# street_light.net
KiCad netlist of a schematic drawn in EAGLE
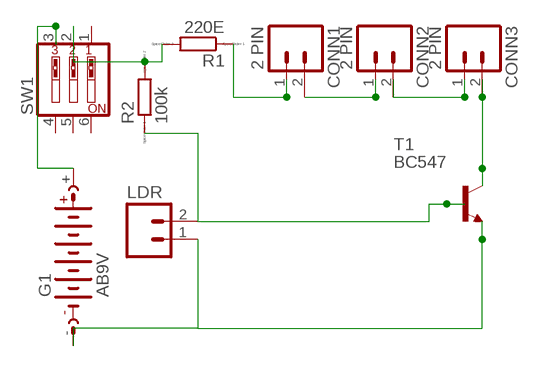
[diagram p0: schematic, sheet 1]

(export (version "E")
  (design (tool "Eeschema 10.0.6"))
  (components
    (comp (ref "CONN1")
      (value "2 PIN")
      (footprint "eagle-import:02P")
      (libsource (lib "eagle-import") (part "M02"))
    )
    (comp (ref "CONN2")
      (value "2 PIN")
      (footprint "eagle-import:02P")
      (libsource (lib "eagle-import") (part "M02"))
    )
    (comp (ref "CONN3")
      (value "2 PIN")
      (footprint "eagle-import:02P")
      (libsource (lib "eagle-import") (part "M02"))
    )
    (comp (ref "G1")
      (value "AB9V")
      (footprint "eagle-import:AB9V")
      (libsource (lib "eagle-import") (part "AB9V"))
    )
    (comp (ref "LDR")
      (value "M02")
      (footprint "eagle-import:02P")
      (libsource (lib "eagle-import") (part "M02"))
    )
    (comp (ref "R1")
      (value "220E")
      (footprint "eagle-import:0204_7")
      (libsource (lib "eagle-import") (part "R0204/7"))
    )
    (comp (ref "R2")
      (value "100k")
      (footprint "eagle-import:0204_7")
      (libsource (lib "eagle-import") (part "R0204/7"))
    )
    (comp (ref "SW1")
      (value "SW_DIP-3")
      (footprint "eagle-import:EDG-03")
      (libsource (lib "eagle-import") (part "SW_DIP-3"))
    )
    (comp (ref "T1")
      (value "BC547")
      (footprint "eagle-import:TO92")
      (libsource (lib "eagle-import") (part "BC547"))
    )
  )
  (nets
    (net (code "1") (name "Net-(CONN1-Pad1)") (class "Default")
      (node (ref "CONN1") (pin "1") (pinfunction "1_1") (pintype "passive"))
      (node (ref "R1") (pin "1") (pinfunction "1_1") (pintype "passive"))
    )
    (net (code "2") (name "Net-(CONN1-Pad2)") (class "Default")
      (node (ref "CONN1") (pin "2") (pinfunction "2_2") (pintype "passive"))
      (node (ref "CONN2") (pin "1") (pinfunction "1_1") (pintype "passive"))
    )
    (net (code "3") (name "Net-(CONN2-Pad2)") (class "Default")
      (node (ref "CONN2") (pin "2") (pinfunction "2_2") (pintype "passive"))
      (node (ref "CONN3") (pin "1") (pinfunction "1_1") (pintype "passive"))
    )
    (net (code "4") (name "Net-(G1-Pad+)") (class "Default")
      (node (ref "G1") (pin "+") (pinfunction "+_+") (pintype "passive"))
      (node (ref "SW1") (pin "3") (pinfunction "3_3") (pintype "passive"))
    )
    (net (code "5") (name "Net-(R1-Pad2)") (class "Default")
      (node (ref "R1") (pin "2") (pinfunction "2_2") (pintype "passive"))
      (node (ref "R2") (pin "2") (pinfunction "2_2") (pintype "passive"))
      (node (ref "SW1") (pin "2") (pinfunction "2_2") (pintype "passive"))
    )
    (net (code "6") (name "Net-(T1-B)") (class "Default")
      (node (ref "LDR") (pin "2") (pinfunction "2_2") (pintype "passive"))
      (node (ref "R2") (pin "1") (pinfunction "1_1") (pintype "passive"))
      (node (ref "T1") (pin "2") (pinfunction "B_2") (pintype "passive"))
    )
    (net (code "7") (name "Net-(T1-C)") (class "Default")
      (node (ref "CONN3") (pin "2") (pinfunction "2_2") (pintype "passive"))
      (node (ref "T1") (pin "3") (pinfunction "C_3") (pintype "passive"))
    )
    (net (code "8") (name "Net-(T1-E)") (class "Default")
      (node (ref "G1") (pin "-") (pinfunction "-_-") (pintype "passive"))
      (node (ref "LDR") (pin "1") (pinfunction "1_1") (pintype "passive"))
      (node (ref "T1") (pin "1") (pinfunction "E_1") (pintype "passive"))
    )
    (net (code "9") (name "unconnected-(SW1-Pad1)") (class "Default")
      (node (ref "SW1") (pin "1") (pinfunction "1_1") (pintype "passive"))
    )
    (net (code "10") (name "unconnected-(SW1-Pad4)") (class "Default")
      (node (ref "SW1") (pin "4") (pinfunction "4_4") (pintype "passive"))
    )
    (net (code "11") (name "unconnected-(SW1-Pad5)") (class "Default")
      (node (ref "SW1") (pin "5") (pinfunction "5_5") (pintype "passive"))
    )
    (net (code "12") (name "unconnected-(SW1-Pad6)") (class "Default")
      (node (ref "SW1") (pin "6") (pinfunction "6_6") (pintype "passive"))
    )
  )
)
